# relay1.net
KiCad netlist of a schematic drawn in Altium Designer
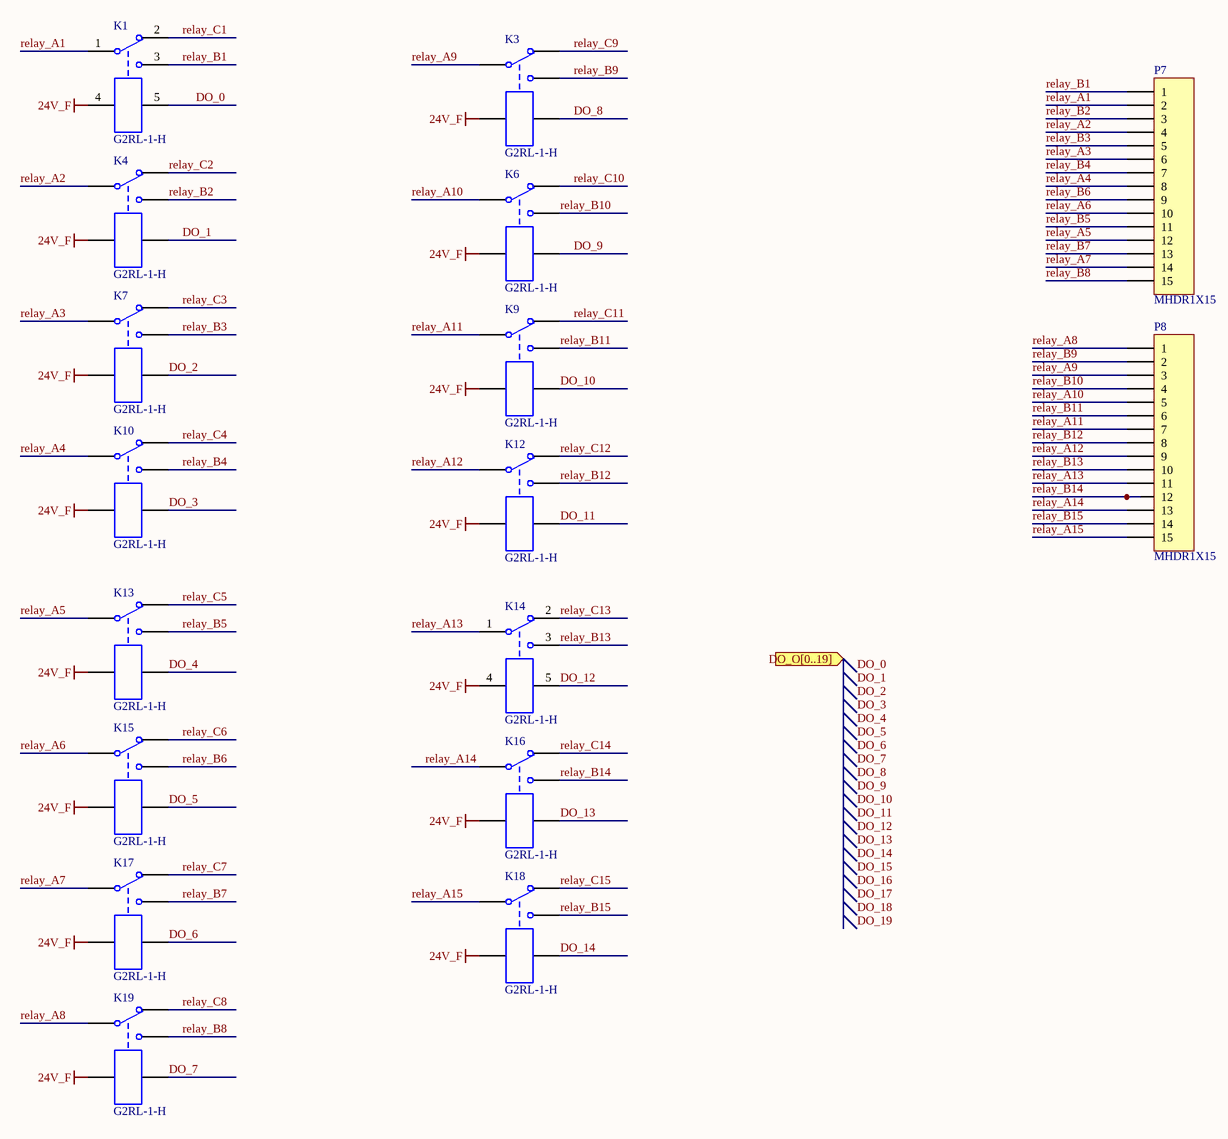
[diagram p0: relay1.SchDoc]

(export (version "E")
  (design (tool "Eeschema 10.0.6"))
  (components
    (comp (ref "K1")
      (value "G2RL-1-H")
      (footprint "G2RL-1-H")
      (description "Single-Pole Dual-Throw Relay")
      (fields (field (name "PUBLISHER") "Altium Limited"))
      (libsource (lib "") (part "Relay-SPDT_1"))
    )
    (comp (ref "K3")
      (value "G2RL-1-H")
      (footprint "G2RL-1-H")
      (description "Single-Pole Dual-Throw Relay")
      (fields (field (name "PUBLISHER") "Altium Limited"))
      (libsource (lib "Miscellaneous Devices") (part "Relay-SPDT"))
    )
    (comp (ref "K4")
      (value "G2RL-1-H")
      (footprint "G2RL-1-H")
      (description "Single-Pole Dual-Throw Relay")
      (fields (field (name "PUBLISHER") "Altium Limited"))
      (libsource (lib "Miscellaneous Devices") (part "Relay-SPDT"))
    )
    (comp (ref "K6")
      (value "G2RL-1-H")
      (footprint "G2RL-1-H")
      (description "Single-Pole Dual-Throw Relay")
      (fields (field (name "PUBLISHER") "Altium Limited"))
      (libsource (lib "Miscellaneous Devices") (part "Relay-SPDT"))
    )
    (comp (ref "K7")
      (value "G2RL-1-H")
      (footprint "G2RL-1-H")
      (description "Single-Pole Dual-Throw Relay")
      (fields (field (name "PUBLISHER") "Altium Limited"))
      (libsource (lib "Miscellaneous Devices") (part "Relay-SPDT"))
    )
    (comp (ref "K9")
      (value "G2RL-1-H")
      (footprint "G2RL-1-H")
      (description "Single-Pole Dual-Throw Relay")
      (fields (field (name "PUBLISHER") "Altium Limited"))
      (libsource (lib "Miscellaneous Devices") (part "Relay-SPDT"))
    )
    (comp (ref "K10")
      (value "G2RL-1-H")
      (footprint "G2RL-1-H")
      (description "Single-Pole Dual-Throw Relay")
      (fields (field (name "PUBLISHER") "Altium Limited"))
      (libsource (lib "Miscellaneous Devices") (part "Relay-SPDT"))
    )
    (comp (ref "K12")
      (value "G2RL-1-H")
      (footprint "G2RL-1-H")
      (description "Single-Pole Dual-Throw Relay")
      (fields (field (name "PUBLISHER") "Altium Limited"))
      (libsource (lib "Miscellaneous Devices") (part "Relay-SPDT"))
    )
    (comp (ref "K13")
      (value "G2RL-1-H")
      (footprint "G2RL-1-H")
      (description "Single-Pole Dual-Throw Relay")
      (fields (field (name "PUBLISHER") "Altium Limited"))
      (libsource (lib "Miscellaneous Devices") (part "Relay-SPDT"))
    )
    (comp (ref "K14")
      (value "G2RL-1-H")
      (footprint "G2RL-1-H")
      (description "Single-Pole Dual-Throw Relay")
      (fields (field (name "PUBLISHER") "Altium Limited"))
      (libsource (lib "") (part "Relay-SPDT_1"))
    )
    (comp (ref "K15")
      (value "G2RL-1-H")
      (footprint "G2RL-1-H")
      (description "Single-Pole Dual-Throw Relay")
      (fields (field (name "PUBLISHER") "Altium Limited"))
      (libsource (lib "Miscellaneous Devices") (part "Relay-SPDT"))
    )
    (comp (ref "K16")
      (value "G2RL-1-H")
      (footprint "G2RL-1-H")
      (description "Single-Pole Dual-Throw Relay")
      (fields (field (name "PUBLISHER") "Altium Limited"))
      (libsource (lib "Miscellaneous Devices") (part "Relay-SPDT"))
    )
    (comp (ref "K17")
      (value "G2RL-1-H")
      (footprint "G2RL-1-H")
      (description "Single-Pole Dual-Throw Relay")
      (fields (field (name "PUBLISHER") "Altium Limited"))
      (libsource (lib "Miscellaneous Devices") (part "Relay-SPDT"))
    )
    (comp (ref "K18")
      (value "G2RL-1-H")
      (footprint "G2RL-1-H")
      (description "Single-Pole Dual-Throw Relay")
      (fields (field (name "PUBLISHER") "Altium Limited"))
      (libsource (lib "Miscellaneous Devices") (part "Relay-SPDT"))
    )
    (comp (ref "K19")
      (value "G2RL-1-H")
      (footprint "G2RL-1-H")
      (description "Single-Pole Dual-Throw Relay")
      (fields (field (name "PUBLISHER") "Altium Limited"))
      (libsource (lib "Miscellaneous Devices") (part "Relay-SPDT"))
    )
    (comp (ref "P7")
      (value "MHDR1X15")
      (footprint "2ETYR-5.08-15P-14-100")
      (description "Header, 15-Pin")
      (fields (field (name "PUBLISHER") "Altium Limited"))
      (libsource (lib "Miscellaneous Connectors") (part "MHDR1X15"))
    )
    (comp (ref "P8")
      (value "MHDR1X15")
      (footprint "2ETYR-5.08-15P-14-100")
      (description "Header, 15-Pin")
      (fields (field (name "PUBLISHER") "Altium Limited"))
      (libsource (lib "Miscellaneous Connectors") (part "MHDR1X15"))
    )
  )
  (nets
    (net (code "21") (name "/DO_0") (class "Default")
      (node (ref "K1") (pin "5") (pinfunction "5_5") (pintype "passive"))
    )
    (net (code "22") (name "/DO_1") (class "Default")
      (node (ref "K4") (pin "5") (pinfunction "5_5") (pintype "passive"))
    )
    (net (code "23") (name "/DO_2") (class "Default")
      (node (ref "K7") (pin "5") (pinfunction "5_5") (pintype "passive"))
    )
    (net (code "24") (name "/DO_3") (class "Default")
      (node (ref "K10") (pin "5") (pinfunction "5_5") (pintype "passive"))
    )
    (net (code "25") (name "/DO_4") (class "Default")
      (node (ref "K13") (pin "5") (pinfunction "5_5") (pintype "passive"))
    )
    (net (code "26") (name "/DO_5") (class "Default")
      (node (ref "K15") (pin "5") (pinfunction "5_5") (pintype "passive"))
    )
    (net (code "27") (name "/DO_6") (class "Default")
      (node (ref "K17") (pin "5") (pinfunction "5_5") (pintype "passive"))
    )
    (net (code "28") (name "/DO_7") (class "Default")
      (node (ref "K19") (pin "5") (pinfunction "5_5") (pintype "passive"))
    )
    (net (code "29") (name "/DO_8") (class "Default")
      (node (ref "K3") (pin "5") (pinfunction "5_5") (pintype "passive"))
    )
    (net (code "30") (name "/DO_9") (class "Default")
      (node (ref "K6") (pin "5") (pinfunction "5_5") (pintype "passive"))
    )
    (net (code "31") (name "/DO_10") (class "Default")
      (node (ref "K9") (pin "5") (pinfunction "5_5") (pintype "passive"))
    )
    (net (code "32") (name "/DO_11") (class "Default")
      (node (ref "K12") (pin "5") (pinfunction "5_5") (pintype "passive"))
    )
    (net (code "33") (name "/DO_12") (class "Default")
      (node (ref "K14") (pin "5") (pinfunction "5_5") (pintype "passive"))
    )
    (net (code "34") (name "/DO_13") (class "Default")
      (node (ref "K16") (pin "5") (pinfunction "5_5") (pintype "passive"))
    )
    (net (code "35") (name "/DO_14") (class "Default")
      (node (ref "K18") (pin "5") (pinfunction "5_5") (pintype "passive"))
    )
    (net (code "42") (name "/relay_A1") (class "Default")
      (node (ref "K1") (pin "1") (pinfunction "1_1") (pintype "passive"))
      (node (ref "P7") (pin "2") (pinfunction "2_2") (pintype "passive"))
    )
    (net (code "43") (name "/relay_A2") (class "Default")
      (node (ref "K4") (pin "1") (pinfunction "1_1") (pintype "passive"))
      (node (ref "P7") (pin "4") (pinfunction "4_4") (pintype "passive"))
    )
    (net (code "44") (name "/relay_A3") (class "Default")
      (node (ref "K7") (pin "1") (pinfunction "1_1") (pintype "passive"))
      (node (ref "P7") (pin "6") (pinfunction "6_6") (pintype "passive"))
    )
    (net (code "45") (name "/relay_A4") (class "Default")
      (node (ref "K10") (pin "1") (pinfunction "1_1") (pintype "passive"))
      (node (ref "P7") (pin "8") (pinfunction "8_8") (pintype "passive"))
    )
    (net (code "46") (name "/relay_A5") (class "Default")
      (node (ref "K13") (pin "1") (pinfunction "1_1") (pintype "passive"))
      (node (ref "P7") (pin "12") (pinfunction "12_12") (pintype "passive"))
    )
    (net (code "47") (name "/relay_A6") (class "Default")
      (node (ref "K15") (pin "1") (pinfunction "1_1") (pintype "passive"))
      (node (ref "P7") (pin "10") (pinfunction "10_10") (pintype "passive"))
    )
    (net (code "48") (name "/relay_A7") (class "Default")
      (node (ref "K17") (pin "1") (pinfunction "1_1") (pintype "passive"))
      (node (ref "P7") (pin "14") (pinfunction "14_14") (pintype "passive"))
    )
    (net (code "49") (name "/relay_A8") (class "Default")
      (node (ref "K19") (pin "1") (pinfunction "1_1") (pintype "passive"))
      (node (ref "P8") (pin "1") (pinfunction "1_1") (pintype "passive"))
    )
    (net (code "50") (name "/relay_A9") (class "Default")
      (node (ref "K3") (pin "1") (pinfunction "1_1") (pintype "passive"))
      (node (ref "P8") (pin "3") (pinfunction "3_3") (pintype "passive"))
    )
    (net (code "51") (name "/relay_A10") (class "Default")
      (node (ref "K6") (pin "1") (pinfunction "1_1") (pintype "passive"))
      (node (ref "P8") (pin "5") (pinfunction "5_5") (pintype "passive"))
    )
    (net (code "52") (name "/relay_A11") (class "Default")
      (node (ref "K9") (pin "1") (pinfunction "1_1") (pintype "passive"))
      (node (ref "P8") (pin "7") (pinfunction "7_7") (pintype "passive"))
    )
    (net (code "53") (name "/relay_A12") (class "Default")
      (node (ref "K12") (pin "1") (pinfunction "1_1") (pintype "passive"))
      (node (ref "P8") (pin "9") (pinfunction "9_9") (pintype "passive"))
    )
    (net (code "54") (name "/relay_A13") (class "Default")
      (node (ref "K14") (pin "1") (pinfunction "1_1") (pintype "passive"))
      (node (ref "P8") (pin "11") (pinfunction "11_11") (pintype "passive"))
    )
    (net (code "55") (name "/relay_A14") (class "Default")
      (node (ref "K16") (pin "1") (pinfunction "1_1") (pintype "passive"))
      (node (ref "P8") (pin "13") (pinfunction "13_13") (pintype "passive"))
    )
    (net (code "56") (name "/relay_A15") (class "Default")
      (node (ref "K18") (pin "1") (pinfunction "1_1") (pintype "passive"))
      (node (ref "P8") (pin "15") (pinfunction "15_15") (pintype "passive"))
    )
    (net (code "57") (name "/relay_B1") (class "Default")
      (node (ref "K1") (pin "3") (pinfunction "3_3") (pintype "passive"))
      (node (ref "P7") (pin "1") (pinfunction "1_1") (pintype "passive"))
    )
    (net (code "58") (name "/relay_B2") (class "Default")
      (node (ref "K4") (pin "3") (pinfunction "3_3") (pintype "passive"))
      (node (ref "P7") (pin "3") (pinfunction "3_3") (pintype "passive"))
    )
    (net (code "59") (name "/relay_B3") (class "Default")
      (node (ref "K7") (pin "3") (pinfunction "3_3") (pintype "passive"))
      (node (ref "P7") (pin "5") (pinfunction "5_5") (pintype "passive"))
    )
    (net (code "60") (name "/relay_B4") (class "Default")
      (node (ref "K10") (pin "3") (pinfunction "3_3") (pintype "passive"))
      (node (ref "P7") (pin "7") (pinfunction "7_7") (pintype "passive"))
    )
    (net (code "61") (name "/relay_B5") (class "Default")
      (node (ref "K13") (pin "3") (pinfunction "3_3") (pintype "passive"))
      (node (ref "P7") (pin "11") (pinfunction "11_11") (pintype "passive"))
    )
    (net (code "62") (name "/relay_B6") (class "Default")
      (node (ref "K15") (pin "3") (pinfunction "3_3") (pintype "passive"))
      (node (ref "P7") (pin "9") (pinfunction "9_9") (pintype "passive"))
    )
    (net (code "63") (name "/relay_B7") (class "Default")
      (node (ref "K17") (pin "3") (pinfunction "3_3") (pintype "passive"))
      (node (ref "P7") (pin "13") (pinfunction "13_13") (pintype "passive"))
    )
    (net (code "64") (name "/relay_B8") (class "Default")
      (node (ref "K19") (pin "3") (pinfunction "3_3") (pintype "passive"))
      (node (ref "P7") (pin "15") (pinfunction "15_15") (pintype "passive"))
    )
    (net (code "65") (name "/relay_B9") (class "Default")
      (node (ref "K3") (pin "3") (pinfunction "3_3") (pintype "passive"))
      (node (ref "P8") (pin "2") (pinfunction "2_2") (pintype "passive"))
    )
    (net (code "66") (name "/relay_B10") (class "Default")
      (node (ref "K6") (pin "3") (pinfunction "3_3") (pintype "passive"))
      (node (ref "P8") (pin "4") (pinfunction "4_4") (pintype "passive"))
    )
    (net (code "67") (name "/relay_B11") (class "Default")
      (node (ref "K9") (pin "3") (pinfunction "3_3") (pintype "passive"))
      (node (ref "P8") (pin "6") (pinfunction "6_6") (pintype "passive"))
    )
    (net (code "68") (name "/relay_B12") (class "Default")
      (node (ref "K12") (pin "3") (pinfunction "3_3") (pintype "passive"))
      (node (ref "P8") (pin "8") (pinfunction "8_8") (pintype "passive"))
    )
    (net (code "69") (name "/relay_B13") (class "Default")
      (node (ref "K14") (pin "3") (pinfunction "3_3") (pintype "passive"))
      (node (ref "P8") (pin "10") (pinfunction "10_10") (pintype "passive"))
    )
    (net (code "70") (name "/relay_B14") (class "Default")
      (node (ref "K16") (pin "3") (pinfunction "3_3") (pintype "passive"))
      (node (ref "P8") (pin "12") (pinfunction "12_12") (pintype "passive"))
    )
    (net (code "71") (name "/relay_B15") (class "Default")
      (node (ref "K18") (pin "3") (pinfunction "3_3") (pintype "passive"))
      (node (ref "P8") (pin "14") (pinfunction "14_14") (pintype "passive"))
    )
    (net (code "72") (name "/relay_C1") (class "Default")
      (node (ref "K1") (pin "2") (pinfunction "2_2") (pintype "passive"))
    )
    (net (code "73") (name "/relay_C2") (class "Default")
      (node (ref "K4") (pin "2") (pinfunction "2_2") (pintype "passive"))
    )
    (net (code "74") (name "/relay_C3") (class "Default")
      (node (ref "K7") (pin "2") (pinfunction "2_2") (pintype "passive"))
    )
    (net (code "75") (name "/relay_C4") (class "Default")
      (node (ref "K10") (pin "2") (pinfunction "2_2") (pintype "passive"))
    )
    (net (code "76") (name "/relay_C5") (class "Default")
      (node (ref "K13") (pin "2") (pinfunction "2_2") (pintype "passive"))
    )
    (net (code "77") (name "/relay_C6") (class "Default")
      (node (ref "K15") (pin "2") (pinfunction "2_2") (pintype "passive"))
    )
    (net (code "78") (name "/relay_C7") (class "Default")
      (node (ref "K17") (pin "2") (pinfunction "2_2") (pintype "passive"))
    )
    (net (code "79") (name "/relay_C8") (class "Default")
      (node (ref "K19") (pin "2") (pinfunction "2_2") (pintype "passive"))
    )
    (net (code "80") (name "/relay_C9") (class "Default")
      (node (ref "K3") (pin "2") (pinfunction "2_2") (pintype "passive"))
    )
    (net (code "81") (name "/relay_C10") (class "Default")
      (node (ref "K6") (pin "2") (pinfunction "2_2") (pintype "passive"))
    )
    (net (code "82") (name "/relay_C11") (class "Default")
      (node (ref "K9") (pin "2") (pinfunction "2_2") (pintype "passive"))
    )
    (net (code "83") (name "/relay_C12") (class "Default")
      (node (ref "K12") (pin "2") (pinfunction "2_2") (pintype "passive"))
    )
    (net (code "84") (name "/relay_C13") (class "Default")
      (node (ref "K14") (pin "2") (pinfunction "2_2") (pintype "passive"))
    )
    (net (code "85") (name "/relay_C14") (class "Default")
      (node (ref "K16") (pin "2") (pinfunction "2_2") (pintype "passive"))
    )
    (net (code "86") (name "/relay_C15") (class "Default")
      (node (ref "K18") (pin "2") (pinfunction "2_2") (pintype "passive"))
    )
    (net (code "87") (name "24V_F") (class "Default")
      (node (ref "K1") (pin "4") (pinfunction "4_4") (pintype "passive"))
      (node (ref "K10") (pin "4") (pinfunction "4_4") (pintype "passive"))
      (node (ref "K12") (pin "4") (pinfunction "4_4") (pintype "passive"))
      (node (ref "K13") (pin "4") (pinfunction "4_4") (pintype "passive"))
      (node (ref "K14") (pin "4") (pinfunction "4_4") (pintype "passive"))
      (node (ref "K15") (pin "4") (pinfunction "4_4") (pintype "passive"))
      (node (ref "K16") (pin "4") (pinfunction "4_4") (pintype "passive"))
      (node (ref "K17") (pin "4") (pinfunction "4_4") (pintype "passive"))
      (node (ref "K18") (pin "4") (pinfunction "4_4") (pintype "passive"))
      (node (ref "K19") (pin "4") (pinfunction "4_4") (pintype "passive"))
      (node (ref "K3") (pin "4") (pinfunction "4_4") (pintype "passive"))
      (node (ref "K4") (pin "4") (pinfunction "4_4") (pintype "passive"))
      (node (ref "K6") (pin "4") (pinfunction "4_4") (pintype "passive"))
      (node (ref "K7") (pin "4") (pinfunction "4_4") (pintype "passive"))
      (node (ref "K9") (pin "4") (pinfunction "4_4") (pintype "passive"))
    )
  )
)
